# 128x16bit_SPI_EEPROM.net
KiCad netlist of a schematic drawn in Altium Designer
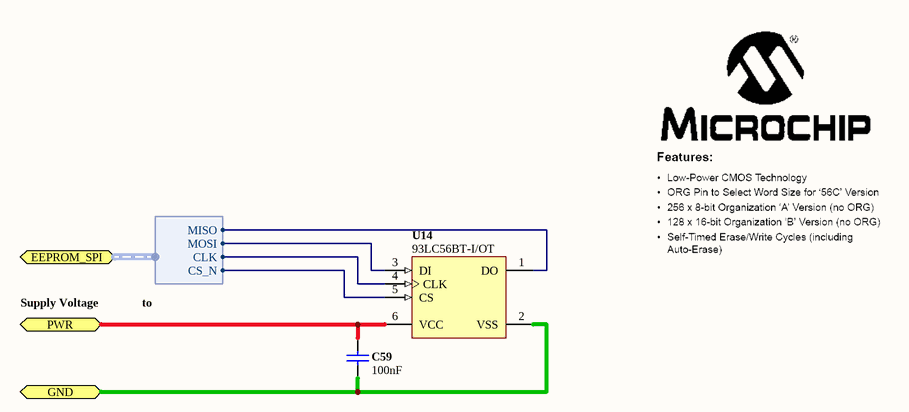
[diagram p0: 128x16bit_SPI_EEPROM.SchDoc]

(export (version "E")
  (design (tool "Eeschema 10.0.6"))
  (components
    (comp (ref "C59")
      (value "100nF")
      (footprint "CAPC0402(1005)60_N")
      (description "CAP 100nF 10V ±10% 0402 (1005 Metric) Thickness 0.6mm SMD")
      (fields (field (name "TOLERANCE") "±10%") (field (name "Comment") "CAP 100nF 10V 0402(1005)"))
      (libsource (lib "Altium Vault") (part "CMP-1034-02065-1"))
    )
    (comp (ref "U14")
      (value "93LC56BT-I/OT")
      (footprint "SOT-23-OT6_N")
      (description "2K, 128x16-bit, 2.5V Microwire Serial EEPROM, 6-Pin SOT-23, Industrial Temperature, Tape and Reel")
      (libsource (lib "Altium Vault") (part "CMP-0162-00356-1"))
    )
  )
  (nets
    (net (code "2") (name "/CLK") (class "Default")
      (node (ref "U14") (pin "4") (pinfunction "CLK_4") (pintype "input"))
    )
    (net (code "3") (name "/CS_N") (class "Default")
      (node (ref "U14") (pin "5") (pinfunction "CS_5") (pintype "input"))
    )
    (net (code "4") (name "/GND") (class "Default")
      (node (ref "C59") (pin "2") (pinfunction "2_2") (pintype "passive"))
      (node (ref "U14") (pin "2") (pinfunction "VSS_2") (pintype "power_in"))
    )
    (net (code "5") (name "/MISO") (class "Default")
      (node (ref "U14") (pin "1") (pinfunction "DO_1") (pintype "tri_state"))
    )
    (net (code "6") (name "/MOSI") (class "Default")
      (node (ref "U14") (pin "3") (pinfunction "DI_3") (pintype "input"))
    )
    (net (code "7") (name "/PWR") (class "Default")
      (node (ref "C59") (pin "1") (pinfunction "1_1") (pintype "passive"))
      (node (ref "U14") (pin "6") (pinfunction "VCC_6") (pintype "power_in"))
    )
  )
)
